# mochila_full.net
KiCad netlist of a schematic drawn in EAGLE
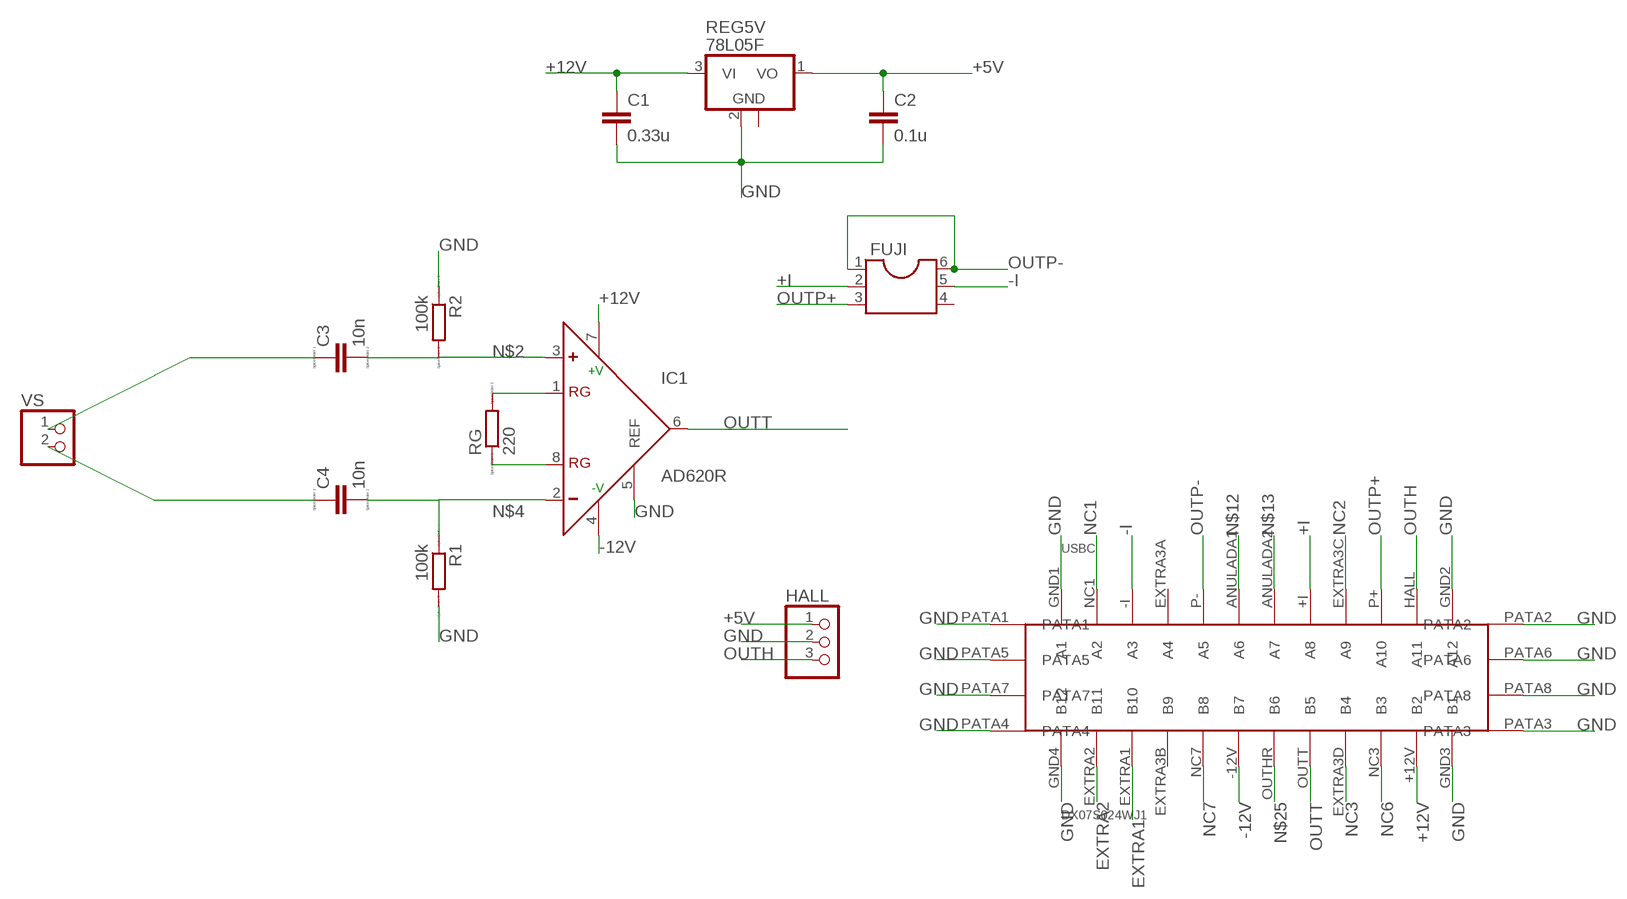
[diagram p0: schematic, sheet 1]

(export (version "E")
  (design (tool "Eeschema 10.0.6"))
  (components
    (comp (ref "C1")
      (value "0.33u")
      (footprint "eagle-import:C0805")
      (libsource (lib "eagle-import") (part "C-EUC0805"))
    )
    (comp (ref "C2")
      (value "0.1u")
      (footprint "eagle-import:C0805")
      (libsource (lib "eagle-import") (part "C-EUC0805"))
    )
    (comp (ref "C3")
      (value "10n")
      (footprint "eagle-import:C0805")
      (libsource (lib "eagle-import") (part "C"))
    )
    (comp (ref "C4")
      (value "10n")
      (footprint "eagle-import:C0805")
      (libsource (lib "eagle-import") (part "C"))
    )
    (comp (ref "FUJI")
      (value "DIL6")
      (footprint "eagle-import:DIL06")
      (libsource (lib "eagle-import") (part "DIL6"))
    )
    (comp (ref "HALL")
      (value "PINHD-1X3")
      (footprint "eagle-import:1X03")
      (libsource (lib "eagle-import") (part "PINHD-1X3"))
    )
    (comp (ref "IC1")
      (value "AD620R")
      (footprint "eagle-import:SO8")
      (fields (field (name "MPN") "AD620AR"))
      (libsource (lib "eagle-import") (part "AD620R"))
    )
    (comp (ref "R1")
      (value "100k")
      (footprint "eagle-import:R0805")
      (libsource (lib "eagle-import") (part "R"))
    )
    (comp (ref "R2")
      (value "100k")
      (footprint "eagle-import:R0805")
      (libsource (lib "eagle-import") (part "R"))
    )
    (comp (ref "REG5V")
      (value "78L05F")
      (footprint "eagle-import:SOT89")
      (libsource (lib "eagle-import") (part "78LF05"))
    )
    (comp (ref "RG")
      (value "220")
      (footprint "eagle-import:R0805")
      (libsource (lib "eagle-import") (part "R"))
    )
    (comp (ref "USBC")
      (value "DX07S024WJ1")
      (footprint "eagle-import:DX07S024WJ1")
      (libsource (lib "eagle-import") (part "DX07S024WJ1"))
    )
    (comp (ref "VS")
      (value "PINHD-1X2")
      (footprint "eagle-import:1X02")
      (libsource (lib "eagle-import") (part "PINHD-1X2"))
    )
  )
  (nets
    (net (code "1") (name "/+5V") (class "Default")
      (node (ref "C2") (pin "1") (pinfunction "1_1") (pintype "passive"))
      (node (ref "HALL") (pin "1") (pinfunction "1_1") (pintype "passive"))
      (node (ref "REG5V") (pin "1") (pinfunction "VO_1") (pintype "passive"))
    )
    (net (code "2") (name "/+12V") (class "Default")
      (node (ref "C1") (pin "1") (pinfunction "1_1") (pintype "passive"))
      (node (ref "IC1") (pin "7") (pinfunction "+V_7") (pintype "power_in"))
      (node (ref "REG5V") (pin "3") (pinfunction "VI_3") (pintype "input"))
      (node (ref "USBC") (pin "+12V") (pinfunction "B2_+12V") (pintype "bidirectional"))
    )
    (net (code "3") (name "/+I") (class "Default")
      (node (ref "FUJI") (pin "2") (pinfunction "2_2") (pintype "passive"))
      (node (ref "USBC") (pin "+I") (pinfunction "A8_+I") (pintype "bidirectional"))
    )
    (net (code "4") (name "/-12V") (class "Default")
      (node (ref "IC1") (pin "4") (pinfunction "-V_4") (pintype "power_in"))
      (node (ref "USBC") (pin "-12V") (pinfunction "B7_-12V") (pintype "bidirectional"))
    )
    (net (code "5") (name "/-I") (class "Default")
      (node (ref "FUJI") (pin "5") (pinfunction "5_5") (pintype "passive"))
      (node (ref "USBC") (pin "-I") (pinfunction "A3_-I") (pintype "bidirectional"))
    )
    (net (code "6") (name "/EXTRA1") (class "Default")
      (node (ref "USBC") (pin "EXTRA1") (pinfunction "B10_EXTRA1") (pintype "bidirectional"))
    )
    (net (code "7") (name "/EXTRA2") (class "Default")
      (node (ref "USBC") (pin "EXTRA2") (pinfunction "B11_EXTRA2") (pintype "bidirectional"))
    )
    (net (code "8") (name "/GND") (class "Default")
      (node (ref "C1") (pin "2") (pinfunction "2_2") (pintype "passive"))
      (node (ref "C2") (pin "2") (pinfunction "2_2") (pintype "passive"))
      (node (ref "HALL") (pin "2") (pinfunction "2_2") (pintype "passive"))
      (node (ref "IC1") (pin "5") (pinfunction "REF_5") (pintype "passive"))
      (node (ref "R1") (pin "2") (pinfunction "2_2") (pintype "passive"))
      (node (ref "R2") (pin "1") (pinfunction "1_1") (pintype "passive"))
      (node (ref "REG5V") (pin "2") (pinfunction "GND_2") (pintype "passive"))
      (node (ref "USBC") (pin "GND1") (pinfunction "A1_GND1") (pintype "bidirectional"))
      (node (ref "USBC") (pin "GND2") (pinfunction "A12_GND2") (pintype "bidirectional"))
      (node (ref "USBC") (pin "GND3") (pinfunction "B1_GND3") (pintype "bidirectional"))
      (node (ref "USBC") (pin "GND4") (pinfunction "B12_GND4") (pintype "bidirectional"))
      (node (ref "USBC") (pin "PATA1") (pinfunction "PATA1_PATA1") (pintype "passive"))
      (node (ref "USBC") (pin "PATA2") (pinfunction "PATA2_PATA2") (pintype "passive"))
      (node (ref "USBC") (pin "PATA3") (pinfunction "PATA3_PATA3") (pintype "passive"))
      (node (ref "USBC") (pin "PATA4") (pinfunction "PATA4_PATA4") (pintype "passive"))
      (node (ref "USBC") (pin "PATA5") (pinfunction "PATA5_PATA5") (pintype "passive"))
      (node (ref "USBC") (pin "PATA6") (pinfunction "PATA6_PATA6") (pintype "passive"))
      (node (ref "USBC") (pin "PATA7") (pinfunction "PATA7_PATA7") (pintype "passive"))
      (node (ref "USBC") (pin "PATA8") (pinfunction "PATA8_PATA8") (pintype "passive"))
    )
    (net (code "9") (name "/N$2") (class "Default")
      (node (ref "C3") (pin "2") (pinfunction "2_2") (pintype "passive"))
      (node (ref "IC1") (pin "3") (pinfunction "+_3") (pintype "input"))
      (node (ref "R2") (pin "2") (pinfunction "2_2") (pintype "passive"))
    )
    (net (code "10") (name "/N$4") (class "Default")
      (node (ref "C4") (pin "2") (pinfunction "2_2") (pintype "passive"))
      (node (ref "IC1") (pin "2") (pinfunction "-_2") (pintype "input"))
      (node (ref "R1") (pin "1") (pinfunction "1_1") (pintype "passive"))
    )
    (net (code "11") (name "/N$12") (class "Default")
      (node (ref "USBC") (pin "ANULADA1") (pinfunction "A6_ANULADA1") (pintype "bidirectional"))
    )
    (net (code "12") (name "/N$13") (class "Default")
      (node (ref "USBC") (pin "ANULADA2") (pinfunction "A7_ANULADA2") (pintype "bidirectional"))
    )
    (net (code "13") (name "/N$25") (class "Default")
      (node (ref "USBC") (pin "OUTHR") (pinfunction "B6_OUTHR") (pintype "bidirectional"))
    )
    (net (code "14") (name "/NC1") (class "Default")
      (node (ref "USBC") (pin "NC1") (pinfunction "A2_NC1") (pintype "bidirectional"))
    )
    (net (code "15") (name "/NC2") (class "Default")
      (node (ref "USBC") (pin "EXTRA3C") (pinfunction "A9_EXTRA3C") (pintype "bidirectional"))
    )
    (net (code "16") (name "/NC3") (class "Default")
      (node (ref "USBC") (pin "EXTRA3D") (pinfunction "B4_EXTRA3D") (pintype "bidirectional"))
    )
    (net (code "17") (name "/NC6") (class "Default")
      (node (ref "USBC") (pin "NC3") (pinfunction "B3_NC3") (pintype "bidirectional"))
    )
    (net (code "18") (name "/NC7") (class "Default")
      (node (ref "USBC") (pin "NC7") (pinfunction "B8_NC7") (pintype "bidirectional"))
    )
    (net (code "19") (name "/OUTH") (class "Default")
      (node (ref "HALL") (pin "3") (pinfunction "3_3") (pintype "passive"))
      (node (ref "USBC") (pin "HALL") (pinfunction "A11_HALL") (pintype "bidirectional"))
    )
    (net (code "20") (name "/OUTP+") (class "Default")
      (node (ref "FUJI") (pin "3") (pinfunction "3_3") (pintype "passive"))
      (node (ref "USBC") (pin "P+") (pinfunction "A10_P+") (pintype "bidirectional"))
    )
    (net (code "21") (name "/OUTP-") (class "Default")
      (node (ref "FUJI") (pin "1") (pinfunction "1_1") (pintype "passive"))
      (node (ref "FUJI") (pin "6") (pinfunction "6_6") (pintype "passive"))
      (node (ref "USBC") (pin "P-") (pinfunction "A5_P-") (pintype "bidirectional"))
    )
    (net (code "22") (name "/OUTT") (class "Default")
      (node (ref "IC1") (pin "6") (pinfunction "OUT_6") (pintype "output"))
      (node (ref "USBC") (pin "OUTT") (pinfunction "B5_OUTT") (pintype "bidirectional"))
    )
    (net (code "23") (name "Net-(C3-Pad1)") (class "Default")
      (node (ref "C3") (pin "1") (pinfunction "1_1") (pintype "passive"))
      (node (ref "VS") (pin "1") (pinfunction "1_1") (pintype "passive"))
    )
    (net (code "24") (name "Net-(C4-Pad1)") (class "Default")
      (node (ref "C4") (pin "1") (pinfunction "1_1") (pintype "passive"))
      (node (ref "VS") (pin "2") (pinfunction "2_2") (pintype "passive"))
    )
    (net (code "25") (name "Net-(IC1-RG-Pad1)") (class "Default")
      (node (ref "IC1") (pin "1") (pinfunction "RG_1") (pintype "passive"))
      (node (ref "RG") (pin "2") (pinfunction "2_2") (pintype "passive"))
    )
    (net (code "26") (name "Net-(IC1-RG-Pad8)") (class "Default")
      (node (ref "IC1") (pin "8") (pinfunction "RG_8") (pintype "passive"))
      (node (ref "RG") (pin "1") (pinfunction "1_1") (pintype "passive"))
    )
    (net (code "27") (name "unconnected-(FUJI-Pad4)") (class "Default")
      (node (ref "FUJI") (pin "4") (pinfunction "4_4") (pintype "passive"))
    )
    (net (code "28") (name "unconnected-(REG5V-GND-Pad2@1)") (class "Default")
      (node (ref "REG5V") (pin "2@1") (pinfunction "GND_2@1") (pintype "passive"))
    )
    (net (code "29") (name "unconnected-(USBC-A4-PadEXTRA3A)") (class "Default")
      (node (ref "USBC") (pin "EXTRA3A") (pinfunction "A4_EXTRA3A") (pintype "bidirectional"))
    )
    (net (code "30") (name "unconnected-(USBC-B9-PadEXTRA3B)") (class "Default")
      (node (ref "USBC") (pin "EXTRA3B") (pinfunction "B9_EXTRA3B") (pintype "bidirectional"))
    )
  )
)
